# Zio_Qwiic_RFID_Reader_V2_0.net
KiCad netlist of a schematic drawn in EAGLE
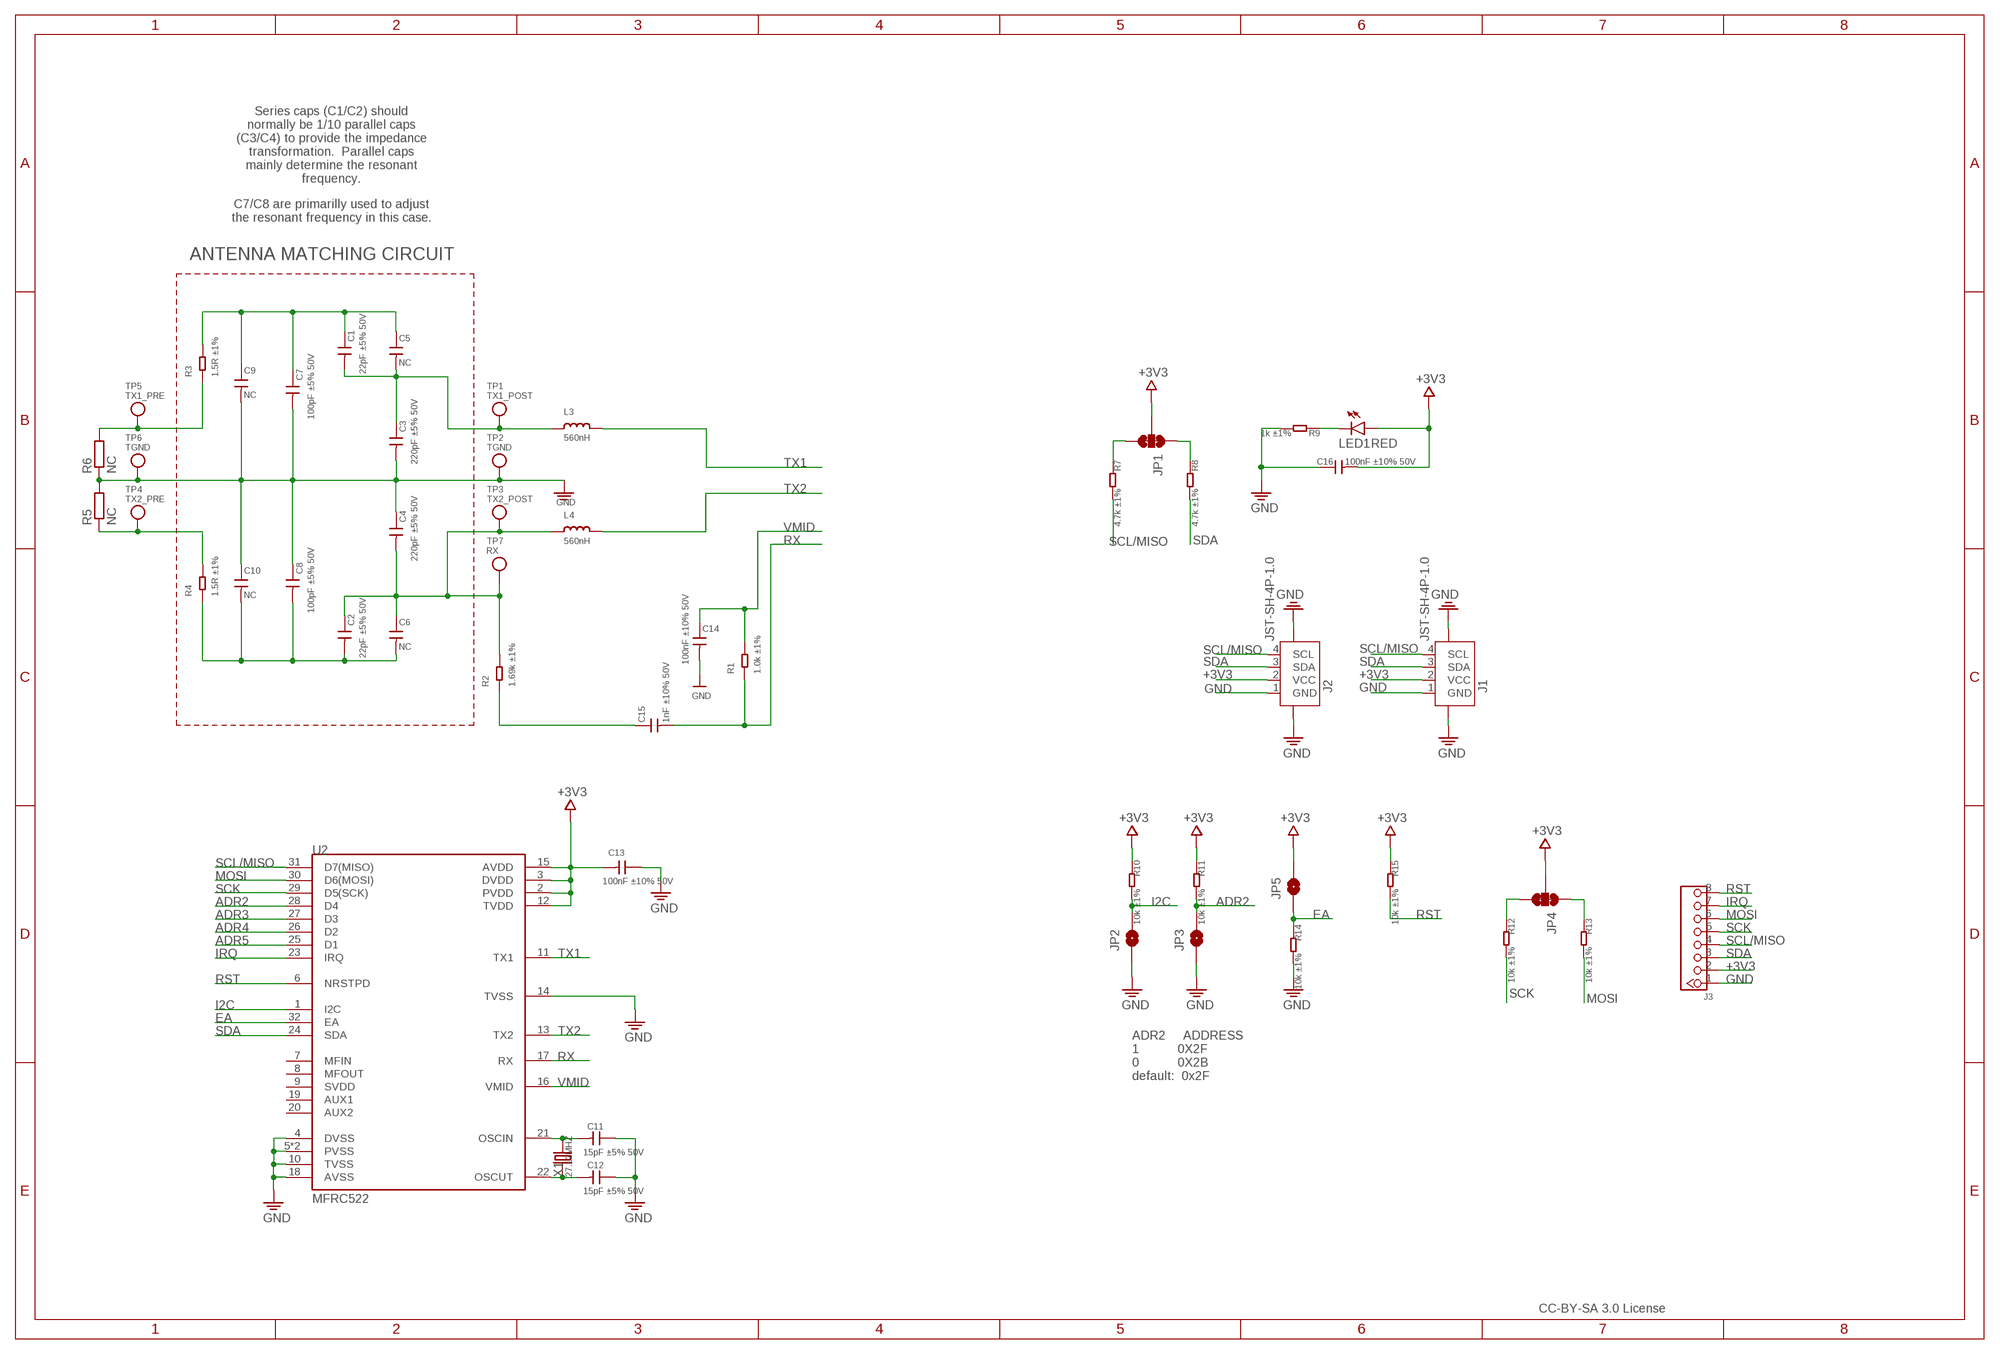
[diagram p0: schematic, sheet 1]

(export (version "E")
  (design (tool "Eeschema 10.0.6"))
  (components
    (comp (ref "C1")
      (value "22pF ±5% 50V")
      (footprint "eagle-import:C0603")
      (libsource (lib "eagle-import") (part "C-0603"))
    )
    (comp (ref "C2")
      (value "22pF ±5% 50V")
      (footprint "eagle-import:C0603")
      (libsource (lib "eagle-import") (part "C-0603"))
    )
    (comp (ref "C3")
      (value "220pF ±5% 50V")
      (footprint "eagle-import:C0603")
      (libsource (lib "eagle-import") (part "C-0603"))
    )
    (comp (ref "C4")
      (value "220pF ±5% 50V")
      (footprint "eagle-import:C0603")
      (libsource (lib "eagle-import") (part "C-0603"))
    )
    (comp (ref "C5")
      (value "NC")
      (footprint "eagle-import:C0603")
      (libsource (lib "eagle-import") (part "C-0603"))
    )
    (comp (ref "C6")
      (value "NC")
      (footprint "eagle-import:C0603")
      (libsource (lib "eagle-import") (part "C-0603"))
    )
    (comp (ref "C7")
      (value "100pF ±5% 50V")
      (footprint "eagle-import:C0603")
      (libsource (lib "eagle-import") (part "C-0603"))
    )
    (comp (ref "C8")
      (value "100pF ±5% 50V")
      (footprint "eagle-import:C0603")
      (libsource (lib "eagle-import") (part "C-0603"))
    )
    (comp (ref "C9")
      (value "NC")
      (footprint "eagle-import:C0603")
      (libsource (lib "eagle-import") (part "C-0603"))
    )
    (comp (ref "C10")
      (value "NC")
      (footprint "eagle-import:C0603")
      (libsource (lib "eagle-import") (part "C-0603"))
    )
    (comp (ref "C11")
      (value "15pF ±5% 50V")
      (footprint "eagle-import:C0603")
      (libsource (lib "eagle-import") (part "C-0603"))
    )
    (comp (ref "C12")
      (value "15pF ±5% 50V")
      (footprint "eagle-import:C0603")
      (libsource (lib "eagle-import") (part "C-0603"))
    )
    (comp (ref "C13")
      (value "100nF ±10% 50V")
      (footprint "eagle-import:C0603")
      (libsource (lib "eagle-import") (part "C-0603"))
    )
    (comp (ref "C14")
      (value "100nF ±10% 50V")
      (footprint "eagle-import:C0603")
      (libsource (lib "eagle-import") (part "C-0603"))
    )
    (comp (ref "C15")
      (value "1nF ±10% 50V")
      (footprint "eagle-import:C0603")
      (libsource (lib "eagle-import") (part "C-0603"))
    )
    (comp (ref "C16")
      (value "100nF ±10% 50V")
      (footprint "eagle-import:C0603")
      (libsource (lib "eagle-import") (part "C-0603"))
    )
    (comp (ref "J1")
      (value "JST-SH-4P-1.0")
      (footprint "eagle-import:JST-SH-4P")
      (libsource (lib "eagle-import") (part "JST-SH-4P-1.0"))
    )
    (comp (ref "J2")
      (value "JST-SH-4P-1.0")
      (footprint "eagle-import:JST-SH-4P")
      (libsource (lib "eagle-import") (part "JST-SH-4P-1.0"))
    )
    (comp (ref "J3")
      (value "HEADER-8P-60/35MIL")
      (footprint "eagle-import:8P-2.54-60_35MIL")
      (libsource (lib "eagle-import") (part "HEADER-8P-60/35MIL"))
    )
    (comp (ref "JP1")
      (value "SMT-JUMPER_3_2-NC_TRACE")
      (footprint "eagle-import:SMT-JUMPER_3_2-NC_TRACE")
      (libsource (lib "eagle-import") (part "SMT-JUMPER_3_2-NC_TRACE"))
    )
    (comp (ref "JP2")
      (value "JUMPER-SMT_2_NC_PASTE_NOCREM")
      (footprint "eagle-import:SMT-JUMPER_2_NC_PASTE_SILK_NOCREM")
      (libsource (lib "eagle-import") (part "JUMPER-SMT_2_NC_PASTE_NOCREM"))
    )
    (comp (ref "JP3")
      (value "JUMPER-SMT_2_NC_PASTE_NOCREM")
      (footprint "eagle-import:SMT-JUMPER_2_NC_PASTE_SILK_NOCREM")
      (libsource (lib "eagle-import") (part "JUMPER-SMT_2_NC_PASTE_NOCREM"))
    )
    (comp (ref "JP4")
      (value "SMT-JUMPER_3_2-NC_TRACE")
      (footprint "eagle-import:SMT-JUMPER_3_2-NC_TRACE")
      (libsource (lib "eagle-import") (part "SMT-JUMPER_3_2-NC_TRACE"))
    )
    (comp (ref "JP5")
      (value "JUMPER-SMT_2_NC_PASTE_NOCREM")
      (footprint "eagle-import:SMT-JUMPER_2_NC_PASTE_SILK_NOCREM")
      (libsource (lib "eagle-import") (part "JUMPER-SMT_2_NC_PASTE_NOCREM"))
    )
    (comp (ref "L3")
      (value "560nH")
      (footprint "eagle-import:0805")
      (libsource (lib "eagle-import") (part "INDUCTOR0805"))
    )
    (comp (ref "L4")
      (value "560nH")
      (footprint "eagle-import:0805")
      (libsource (lib "eagle-import") (part "INDUCTOR0805"))
    )
    (comp (ref "LED1")
      (value "RED")
      (footprint "eagle-import:CHIP-LED0603")
      (libsource (lib "eagle-import") (part "LEDCHIP-LED0603"))
    )
    (comp (ref "R1")
      (value "1.0k ±1%")
      (footprint "eagle-import:R0603")
      (libsource (lib "eagle-import") (part "R-0603"))
    )
    (comp (ref "R2")
      (value "1.69k ±1%")
      (footprint "eagle-import:R0603")
      (libsource (lib "eagle-import") (part "R-0603"))
    )
    (comp (ref "R3")
      (value "1.5R ±1%")
      (footprint "eagle-import:R0603")
      (libsource (lib "eagle-import") (part "R-0603"))
    )
    (comp (ref "R4")
      (value "1.5R ±1%")
      (footprint "eagle-import:R0603")
      (libsource (lib "eagle-import") (part "R-0603"))
    )
    (comp (ref "R5")
      (value "NC")
      (footprint "eagle-import:R0201")
      (libsource (lib "eagle-import") (part "R-EU_R0201"))
    )
    (comp (ref "R6")
      (value "NC")
      (footprint "eagle-import:R0201")
      (libsource (lib "eagle-import") (part "R-EU_R0201"))
    )
    (comp (ref "R7")
      (value "4.7k ±1%")
      (footprint "eagle-import:R0603")
      (libsource (lib "eagle-import") (part "R-0603"))
    )
    (comp (ref "R8")
      (value "4.7k ±1%")
      (footprint "eagle-import:R0603")
      (libsource (lib "eagle-import") (part "R-0603"))
    )
    (comp (ref "R9")
      (value "1k ±1%")
      (footprint "eagle-import:R0603")
      (libsource (lib "eagle-import") (part "R-0603"))
    )
    (comp (ref "R10")
      (value "10k ±1%")
      (footprint "eagle-import:R0603")
      (libsource (lib "eagle-import") (part "R-0603"))
    )
    (comp (ref "R11")
      (value "10k ±1%")
      (footprint "eagle-import:R0603")
      (libsource (lib "eagle-import") (part "R-0603"))
    )
    (comp (ref "R12")
      (value "10k ±1%")
      (footprint "eagle-import:R0603")
      (libsource (lib "eagle-import") (part "R-0603"))
    )
    (comp (ref "R13")
      (value "10k ±1%")
      (footprint "eagle-import:R0603")
      (libsource (lib "eagle-import") (part "R-0603"))
    )
    (comp (ref "R14")
      (value "10k ±1%")
      (footprint "eagle-import:R0603")
      (libsource (lib "eagle-import") (part "R-0603"))
    )
    (comp (ref "R15")
      (value "10k ±1%")
      (footprint "eagle-import:R0603")
      (libsource (lib "eagle-import") (part "R-0603"))
    )
    (comp (ref "TP1")
      (value "TX1_POST")
      (footprint "eagle-import:TESTPOINT_ROUND_1MM")
      (libsource (lib "eagle-import") (part "TESTPOINTROUND1MM"))
    )
    (comp (ref "TP2")
      (value "TGND")
      (footprint "eagle-import:TESTPOINT_ROUND_1MM")
      (libsource (lib "eagle-import") (part "TESTPOINTROUND1MM"))
    )
    (comp (ref "TP3")
      (value "TX2_POST")
      (footprint "eagle-import:TESTPOINT_ROUND_1MM")
      (libsource (lib "eagle-import") (part "TESTPOINTROUND1MM"))
    )
    (comp (ref "TP4")
      (value "TX2_PRE")
      (footprint "eagle-import:TESTPOINT_ROUND_1MM")
      (libsource (lib "eagle-import") (part "TESTPOINTROUND1MM"))
    )
    (comp (ref "TP5")
      (value "TX1_PRE")
      (footprint "eagle-import:TESTPOINT_ROUND_1MM")
      (libsource (lib "eagle-import") (part "TESTPOINTROUND1MM"))
    )
    (comp (ref "TP6")
      (value "TGND")
      (footprint "eagle-import:TESTPOINT_ROUND_1MM")
      (libsource (lib "eagle-import") (part "TESTPOINTROUND1MM"))
    )
    (comp (ref "TP7")
      (value "RX")
      (footprint "eagle-import:TESTPOINT_ROUND_1MM")
      (libsource (lib "eagle-import") (part "TESTPOINTROUND1MM"))
    )
    (comp (ref "U1")
      (value "MFRC522")
      (footprint "eagle-import:HVQFN32")
      (libsource (lib "eagle-import") (part "MFRC522"))
    )
    (comp (ref "X1")
      (value "27.12MHZ")
      (footprint "eagle-import:HC49UP")
      (libsource (lib "eagle-import") (part "CRYSTAL-HC49UP"))
    )
  )
  (nets
    (net (code "1") (name "+3V3") (class "Default")
      (node (ref "C13") (pin "2") (pinfunction "2_2") (pintype "passive"))
      (node (ref "C16") (pin "2") (pinfunction "2_2") (pintype "passive"))
      (node (ref "J1") (pin "2") (pinfunction "VCC_2") (pintype "bidirectional"))
      (node (ref "J2") (pin "2") (pinfunction "VCC_2") (pintype "bidirectional"))
      (node (ref "J3") (pin "2") (pinfunction "2_2") (pintype "bidirectional"))
      (node (ref "JP1") (pin "2") (pinfunction "2_2") (pintype "passive"))
      (node (ref "JP4") (pin "2") (pinfunction "2_2") (pintype "passive"))
      (node (ref "JP5") (pin "2") (pinfunction "2_2") (pintype "passive"))
      (node (ref "LED1") (pin "A") (pinfunction "A_A") (pintype "passive"))
      (node (ref "R10") (pin "1") (pinfunction "1_1") (pintype "passive"))
      (node (ref "R11") (pin "1") (pinfunction "1_1") (pintype "passive"))
      (node (ref "R15") (pin "1") (pinfunction "1_1") (pintype "passive"))
      (node (ref "U1") (pin "12") (pinfunction "TVDD_12") (pintype "bidirectional"))
      (node (ref "U1") (pin "15") (pinfunction "AVDD_15") (pintype "bidirectional"))
      (node (ref "U1") (pin "2") (pinfunction "PVDD_2") (pintype "bidirectional"))
      (node (ref "U1") (pin "3") (pinfunction "DVDD_3") (pintype "bidirectional"))
    )
    (net (code "2") (name "/ADR2") (class "Default")
      (node (ref "JP3") (pin "2") (pinfunction "2_2") (pintype "passive"))
      (node (ref "R11") (pin "2") (pinfunction "2_2") (pintype "passive"))
      (node (ref "U1") (pin "28") (pinfunction "D4_28") (pintype "bidirectional"))
    )
    (net (code "3") (name "/ADR3") (class "Default")
      (node (ref "U1") (pin "27") (pinfunction "D3_27") (pintype "bidirectional"))
    )
    (net (code "4") (name "/ADR4") (class "Default")
      (node (ref "U1") (pin "26") (pinfunction "D2_26") (pintype "bidirectional"))
    )
    (net (code "5") (name "/ADR5") (class "Default")
      (node (ref "U1") (pin "25") (pinfunction "D1_25") (pintype "bidirectional"))
    )
    (net (code "6") (name "/EA") (class "Default")
      (node (ref "JP5") (pin "1") (pinfunction "1_1") (pintype "passive"))
      (node (ref "R14") (pin "1") (pinfunction "1_1") (pintype "passive"))
      (node (ref "U1") (pin "32") (pinfunction "EA_32") (pintype "bidirectional"))
    )
    (net (code "7") (name "/I2C") (class "Default")
      (node (ref "JP2") (pin "2") (pinfunction "2_2") (pintype "passive"))
      (node (ref "R10") (pin "2") (pinfunction "2_2") (pintype "passive"))
      (node (ref "U1") (pin "1") (pinfunction "I2C_1") (pintype "bidirectional"))
    )
    (net (code "8") (name "/IRQ") (class "Default")
      (node (ref "J3") (pin "7") (pinfunction "7_7") (pintype "bidirectional"))
      (node (ref "U1") (pin "23") (pinfunction "IRQ_23") (pintype "bidirectional"))
    )
    (net (code "9") (name "/MOSI") (class "Default")
      (node (ref "J3") (pin "6") (pinfunction "6_6") (pintype "bidirectional"))
      (node (ref "R13") (pin "2") (pinfunction "2_2") (pintype "passive"))
      (node (ref "U1") (pin "30") (pinfunction "D6(MOSI)_30") (pintype "bidirectional"))
    )
    (net (code "10") (name "/RST") (class "Default")
      (node (ref "J3") (pin "8") (pinfunction "8_8") (pintype "bidirectional"))
      (node (ref "R15") (pin "2") (pinfunction "2_2") (pintype "passive"))
      (node (ref "U1") (pin "6") (pinfunction "NRSTPD_6") (pintype "bidirectional"))
    )
    (net (code "11") (name "/RX") (class "Default")
      (node (ref "C15") (pin "2") (pinfunction "2_2") (pintype "passive"))
      (node (ref "R1") (pin "1") (pinfunction "1_1") (pintype "passive"))
      (node (ref "U1") (pin "17") (pinfunction "RX_17") (pintype "bidirectional"))
    )
    (net (code "12") (name "/SCK") (class "Default")
      (node (ref "J3") (pin "5") (pinfunction "5_5") (pintype "bidirectional"))
      (node (ref "R12") (pin "2") (pinfunction "2_2") (pintype "passive"))
      (node (ref "U1") (pin "29") (pinfunction "D5(SCK)_29") (pintype "bidirectional"))
    )
    (net (code "13") (name "/SCL{slash}MISO") (class "Default")
      (node (ref "J1") (pin "4") (pinfunction "SCL_4") (pintype "bidirectional"))
      (node (ref "J2") (pin "4") (pinfunction "SCL_4") (pintype "bidirectional"))
      (node (ref "J3") (pin "4") (pinfunction "4_4") (pintype "bidirectional"))
      (node (ref "R7") (pin "2") (pinfunction "2_2") (pintype "passive"))
      (node (ref "U1") (pin "31") (pinfunction "D7(MISO)_31") (pintype "bidirectional"))
    )
    (net (code "14") (name "/SDA") (class "Default")
      (node (ref "J1") (pin "3") (pinfunction "SDA_3") (pintype "bidirectional"))
      (node (ref "J2") (pin "3") (pinfunction "SDA_3") (pintype "bidirectional"))
      (node (ref "J3") (pin "3") (pinfunction "3_3") (pintype "bidirectional"))
      (node (ref "R8") (pin "2") (pinfunction "2_2") (pintype "passive"))
      (node (ref "U1") (pin "24") (pinfunction "SDA_24") (pintype "bidirectional"))
    )
    (net (code "15") (name "/TX1") (class "Default")
      (node (ref "L3") (pin "2") (pinfunction "2_2") (pintype "passive"))
      (node (ref "U1") (pin "11") (pinfunction "TX1_11") (pintype "bidirectional"))
    )
    (net (code "16") (name "/TX2") (class "Default")
      (node (ref "L4") (pin "2") (pinfunction "2_2") (pintype "passive"))
      (node (ref "U1") (pin "13") (pinfunction "TX2_13") (pintype "bidirectional"))
    )
    (net (code "17") (name "/VMID") (class "Default")
      (node (ref "C14") (pin "1") (pinfunction "1_1") (pintype "passive"))
      (node (ref "R1") (pin "2") (pinfunction "2_2") (pintype "passive"))
      (node (ref "U1") (pin "16") (pinfunction "VMID_16") (pintype "bidirectional"))
    )
    (net (code "18") (name "GND") (class "Default")
      (node (ref "C10") (pin "1") (pinfunction "1_1") (pintype "passive"))
      (node (ref "C11") (pin "1") (pinfunction "1_1") (pintype "passive"))
      (node (ref "C12") (pin "1") (pinfunction "1_1") (pintype "passive"))
      (node (ref "C13") (pin "1") (pinfunction "1_1") (pintype "passive"))
      (node (ref "C14") (pin "2") (pinfunction "2_2") (pintype "passive"))
      (node (ref "C16") (pin "1") (pinfunction "1_1") (pintype "passive"))
      (node (ref "C3") (pin "2") (pinfunction "2_2") (pintype "passive"))
      (node (ref "C4") (pin "1") (pinfunction "1_1") (pintype "passive"))
      (node (ref "C7") (pin "2") (pinfunction "2_2") (pintype "passive"))
      (node (ref "C8") (pin "1") (pinfunction "1_1") (pintype "passive"))
      (node (ref "C9") (pin "2") (pinfunction "2_2") (pintype "passive"))
      (node (ref "J1") (pin "1") (pinfunction "GND_1") (pintype "bidirectional"))
      (node (ref "J1") (pin "NC1") (pinfunction "5_NC1") (pintype "bidirectional"))
      (node (ref "J1") (pin "NC2") (pinfunction "6_NC2") (pintype "bidirectional"))
      (node (ref "J2") (pin "1") (pinfunction "GND_1") (pintype "bidirectional"))
      (node (ref "J2") (pin "NC1") (pinfunction "5_NC1") (pintype "bidirectional"))
      (node (ref "J2") (pin "NC2") (pinfunction "6_NC2") (pintype "bidirectional"))
      (node (ref "J3") (pin "1") (pinfunction "1_1") (pintype "bidirectional"))
      (node (ref "JP2") (pin "1") (pinfunction "1_1") (pintype "passive"))
      (node (ref "JP3") (pin "1") (pinfunction "1_1") (pintype "passive"))
      (node (ref "R14") (pin "2") (pinfunction "2_2") (pintype "passive"))
      (node (ref "R5") (pin "2") (pinfunction "2_2") (pintype "passive"))
      (node (ref "R6") (pin "1") (pinfunction "1_1") (pintype "passive"))
      (node (ref "R9") (pin "2") (pinfunction "2_2") (pintype "passive"))
      (node (ref "TP2") (pin "P$1") (pinfunction "P$1_P$1") (pintype "bidirectional"))
      (node (ref "TP6") (pin "P$1") (pinfunction "P$1_P$1") (pintype "bidirectional"))
      (node (ref "U1") (pin "10") (pinfunction "TVSS_10") (pintype "bidirectional"))
      (node (ref "U1") (pin "14") (pinfunction "TVSS_14") (pintype "bidirectional"))
      (node (ref "U1") (pin "18") (pinfunction "AVSS_18") (pintype "bidirectional"))
      (node (ref "U1") (pin "33") (pinfunction "PVSS_33") (pintype "bidirectional"))
      (node (ref "U1") (pin "4") (pinfunction "DVSS_4") (pintype "bidirectional"))
      (node (ref "U1") (pin "5") (pinfunction "PVSS_5") (pintype "bidirectional"))
    )
    (net (code "19") (name "Net-(C1-Pad1)") (class "Default")
      (node (ref "C1") (pin "1") (pinfunction "1_1") (pintype "passive"))
      (node (ref "C5") (pin "1") (pinfunction "1_1") (pintype "passive"))
      (node (ref "C7") (pin "1") (pinfunction "1_1") (pintype "passive"))
      (node (ref "C9") (pin "1") (pinfunction "1_1") (pintype "passive"))
      (node (ref "R3") (pin "2") (pinfunction "2_2") (pintype "passive"))
    )
    (net (code "20") (name "Net-(C1-Pad2)") (class "Default")
      (node (ref "C1") (pin "2") (pinfunction "2_2") (pintype "passive"))
      (node (ref "C3") (pin "1") (pinfunction "1_1") (pintype "passive"))
      (node (ref "C5") (pin "2") (pinfunction "2_2") (pintype "passive"))
      (node (ref "L3") (pin "1") (pinfunction "1_1") (pintype "passive"))
      (node (ref "TP1") (pin "P$1") (pinfunction "P$1_P$1") (pintype "bidirectional"))
    )
    (net (code "21") (name "Net-(C2-Pad1)") (class "Default")
      (node (ref "C2") (pin "1") (pinfunction "1_1") (pintype "passive"))
      (node (ref "C4") (pin "2") (pinfunction "2_2") (pintype "passive"))
      (node (ref "C6") (pin "1") (pinfunction "1_1") (pintype "passive"))
      (node (ref "L4") (pin "1") (pinfunction "1_1") (pintype "passive"))
      (node (ref "R2") (pin "2") (pinfunction "2_2") (pintype "passive"))
      (node (ref "TP3") (pin "P$1") (pinfunction "P$1_P$1") (pintype "bidirectional"))
      (node (ref "TP7") (pin "P$1") (pinfunction "P$1_P$1") (pintype "bidirectional"))
    )
    (net (code "22") (name "Net-(C10-Pad2)") (class "Default")
      (node (ref "C10") (pin "2") (pinfunction "2_2") (pintype "passive"))
      (node (ref "C2") (pin "2") (pinfunction "2_2") (pintype "passive"))
      (node (ref "C6") (pin "2") (pinfunction "2_2") (pintype "passive"))
      (node (ref "C8") (pin "2") (pinfunction "2_2") (pintype "passive"))
      (node (ref "R4") (pin "1") (pinfunction "1_1") (pintype "passive"))
    )
    (net (code "23") (name "Net-(C15-Pad1)") (class "Default")
      (node (ref "C15") (pin "1") (pinfunction "1_1") (pintype "passive"))
      (node (ref "R2") (pin "1") (pinfunction "1_1") (pintype "passive"))
    )
    (net (code "24") (name "Net-(JP1-Pad1)") (class "Default")
      (node (ref "JP1") (pin "1") (pinfunction "1_1") (pintype "passive"))
      (node (ref "R8") (pin "1") (pinfunction "1_1") (pintype "passive"))
    )
    (net (code "25") (name "Net-(JP1-Pad3)") (class "Default")
      (node (ref "JP1") (pin "3") (pinfunction "3_3") (pintype "passive"))
      (node (ref "R7") (pin "1") (pinfunction "1_1") (pintype "passive"))
    )
    (net (code "26") (name "Net-(JP4-Pad1)") (class "Default")
      (node (ref "JP4") (pin "1") (pinfunction "1_1") (pintype "passive"))
      (node (ref "R13") (pin "1") (pinfunction "1_1") (pintype "passive"))
    )
    (net (code "27") (name "Net-(JP4-Pad3)") (class "Default")
      (node (ref "JP4") (pin "3") (pinfunction "3_3") (pintype "passive"))
      (node (ref "R12") (pin "1") (pinfunction "1_1") (pintype "passive"))
    )
    (net (code "28") (name "Net-(LED1-PadC)") (class "Default")
      (node (ref "LED1") (pin "C") (pinfunction "C_C") (pintype "passive"))
      (node (ref "R9") (pin "1") (pinfunction "1_1") (pintype "passive"))
    )
    (net (code "29") (name "Net-(R3-Pad1)") (class "Default")
      (node (ref "R3") (pin "1") (pinfunction "1_1") (pintype "passive"))
      (node (ref "R6") (pin "2") (pinfunction "2_2") (pintype "passive"))
      (node (ref "TP5") (pin "P$1") (pinfunction "P$1_P$1") (pintype "bidirectional"))
    )
    (net (code "30") (name "Net-(R4-Pad2)") (class "Default")
      (node (ref "R4") (pin "2") (pinfunction "2_2") (pintype "passive"))
      (node (ref "R5") (pin "1") (pinfunction "1_1") (pintype "passive"))
      (node (ref "TP4") (pin "P$1") (pinfunction "P$1_P$1") (pintype "bidirectional"))
    )
    (net (code "31") (name "Net-(U1-OSCIN)") (class "Default")
      (node (ref "C11") (pin "2") (pinfunction "2_2") (pintype "passive"))
      (node (ref "U1") (pin "21") (pinfunction "OSCIN_21") (pintype "bidirectional"))
      (node (ref "X1") (pin "2") (pinfunction "2_2") (pintype "passive"))
    )
    (net (code "32") (name "Net-(U1-OSCUT)") (class "Default")
      (node (ref "C12") (pin "2") (pinfunction "2_2") (pintype "passive"))
      (node (ref "U1") (pin "22") (pinfunction "OSCUT_22") (pintype "bidirectional"))
      (node (ref "X1") (pin "1") (pinfunction "1_1") (pintype "passive"))
    )
    (net (code "33") (name "unconnected-(U1-AUX1-Pad19)") (class "Default")
      (node (ref "U1") (pin "19") (pinfunction "AUX1_19") (pintype "bidirectional"))
    )
    (net (code "34") (name "unconnected-(U1-AUX2-Pad20)") (class "Default")
      (node (ref "U1") (pin "20") (pinfunction "AUX2_20") (pintype "bidirectional"))
    )
    (net (code "35") (name "unconnected-(U1-MFIN-Pad7)") (class "Default")
      (node (ref "U1") (pin "7") (pinfunction "MFIN_7") (pintype "bidirectional"))
    )
    (net (code "36") (name "unconnected-(U1-MFOUT-Pad8)") (class "Default")
      (node (ref "U1") (pin "8") (pinfunction "MFOUT_8") (pintype "bidirectional"))
    )
    (net (code "37") (name "unconnected-(U1-SVDD-Pad9)") (class "Default")
      (node (ref "U1") (pin "9") (pinfunction "SVDD_9") (pintype "bidirectional"))
    )
  )
)
